# GPS_radiologger_v19.net
KiCad netlist of a schematic drawn in EAGLE
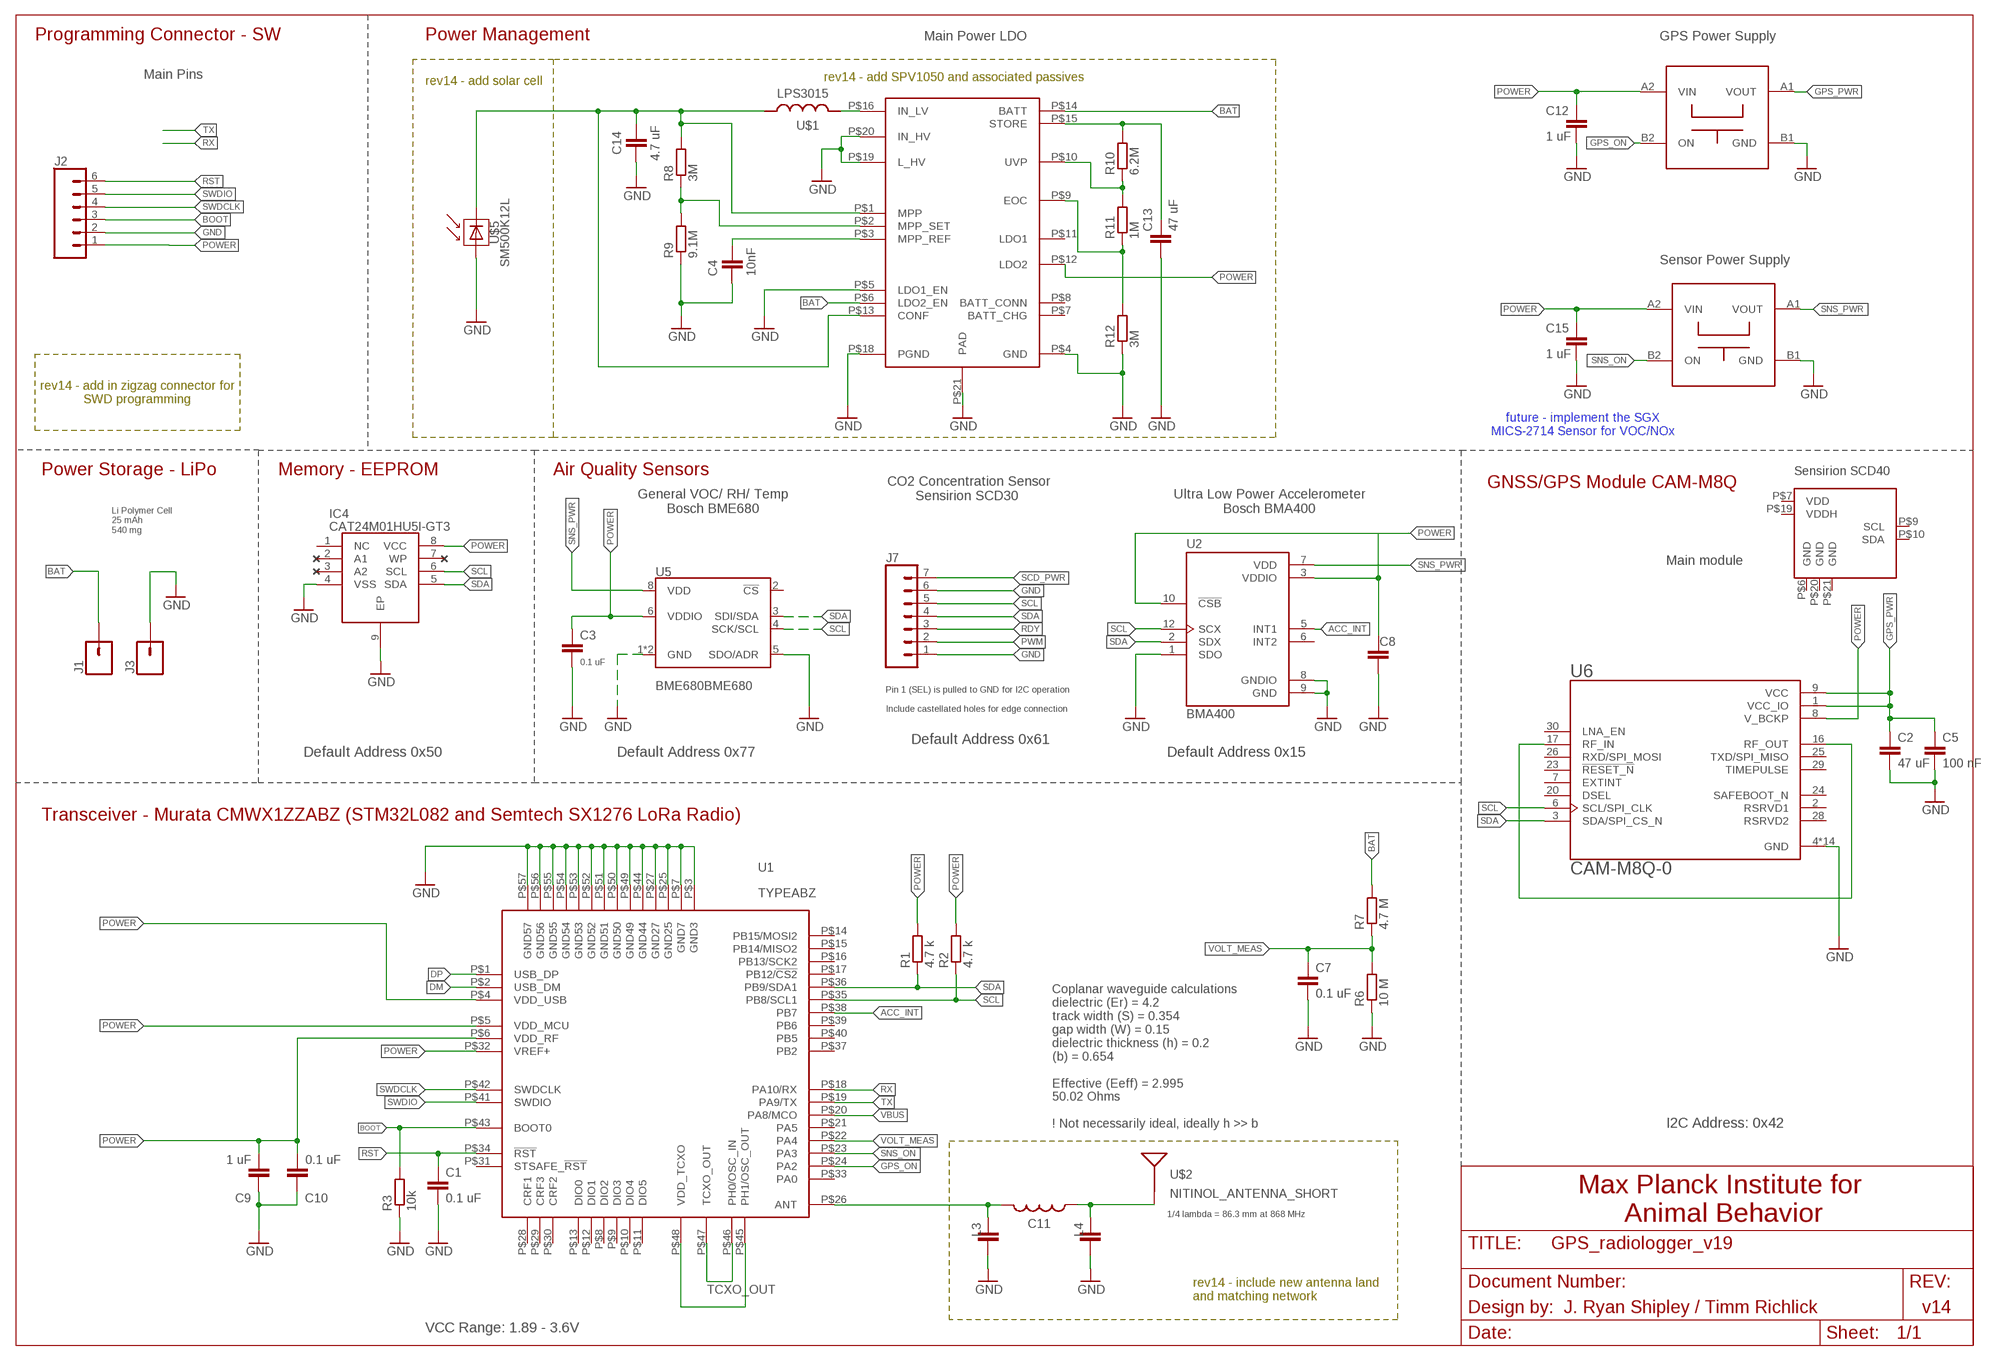
[diagram p0: schematic, sheet 1]

(export (version "E")
  (design (tool "Eeschema 10.0.6"))
  (components
    (comp (ref "C1")
      (value "0.1 uF")
      (footprint "eagle-import:C0201")
      (libsource (lib "eagle-import") (part "C-EUC0201"))
    )
    (comp (ref "C2")
      (value "47 uF")
      (footprint "eagle-import:C0201")
      (libsource (lib "eagle-import") (part "C-EUC0201"))
    )
    (comp (ref "C3")
      (value "0.1 uF")
      (footprint "eagle-import:C0201")
      (libsource (lib "eagle-import") (part "C-EUC0201"))
    )
    (comp (ref "C4")
      (value "10nF")
      (footprint "eagle-import:C0201")
      (libsource (lib "eagle-import") (part "C-EUC0201"))
    )
    (comp (ref "C5")
      (value "100 nF")
      (footprint "eagle-import:C0201")
      (libsource (lib "eagle-import") (part "C-EUC0201"))
    )
    (comp (ref "C7")
      (value "0.1 uF")
      (footprint "eagle-import:C0201")
      (libsource (lib "eagle-import") (part "C-EUC0201"))
    )
    (comp (ref "C8")
      (value "C-EUC0201")
      (footprint "eagle-import:C0201")
      (libsource (lib "eagle-import") (part "C-EUC0201"))
    )
    (comp (ref "C9")
      (value "1 uF")
      (footprint "eagle-import:C0201")
      (libsource (lib "eagle-import") (part "C-EUC0201"))
    )
    (comp (ref "C10")
      (value "0.1 uF")
      (footprint "eagle-import:C0201")
      (libsource (lib "eagle-import") (part "C-EUC0201"))
    )
    (comp (ref "C11")
      (value "0.1uF")
      (footprint "eagle-import:L0201")
      (libsource (lib "eagle-import") (part "L-USL0201"))
    )
    (comp (ref "C12")
      (value "1 uF")
      (footprint "eagle-import:C0201")
      (libsource (lib "eagle-import") (part "C-EUC0201"))
    )
    (comp (ref "C13")
      (value "47 uF")
      (footprint "eagle-import:C0805K")
      (libsource (lib "eagle-import") (part "C-EUC0805K"))
    )
    (comp (ref "C14")
      (value "4.7 uF")
      (footprint "eagle-import:C0201")
      (libsource (lib "eagle-import") (part "C-EUC0201"))
    )
    (comp (ref "C15")
      (value "1 uF")
      (footprint "eagle-import:C0201")
      (libsource (lib "eagle-import") (part "C-EUC0201"))
    )
    (comp (ref "IC4")
      (value "CAT24M01HU5I-GT3")
      (footprint "eagle-import:SON50P300X200X55-9N")
      (fields
        (field (name "MOUSER_PART_NUMBER") "863-CAT24M01HU5I-GT3")
        (field (name "RS_PART_NUMBER") "7814831P")
      )
      (libsource (lib "eagle-import") (part "CAT24M01HU5I-GT3"))
    )
    (comp (ref "J1")
      (value "CONN_01PTH_NO_SILK_YES_STOP")
      (footprint "eagle-import:1X01_NO_SILK")
      (libsource (lib "eagle-import") (part "CONN_01PTH_NO_SILK_YES_STOP"))
    )
    (comp (ref "J2")
      (value "CONN_06NO_SILK_NO_POP")
      (footprint "eagle-import:1X06_NO_SILK")
      (libsource (lib "eagle-import") (part "CONN_06NO_SILK_NO_POP"))
    )
    (comp (ref "J3")
      (value "CONN_01PTH_NO_SILK_YES_STOP")
      (footprint "eagle-import:1X01_NO_SILK")
      (libsource (lib "eagle-import") (part "CONN_01PTH_NO_SILK_YES_STOP"))
    )
    (comp (ref "J7")
      (value "CONN_07NO_SILK")
      (footprint "eagle-import:1X07_NO_SILK")
      (libsource (lib "eagle-import") (part "CONN_07NO_SILK"))
    )
    (comp (ref "L3")
      (value "C-EUC0201")
      (footprint "eagle-import:C0201")
      (libsource (lib "eagle-import") (part "C-EUC0201"))
    )
    (comp (ref "L4")
      (value "C-EUC0201")
      (footprint "eagle-import:C0201")
      (libsource (lib "eagle-import") (part "C-EUC0201"))
    )
    (comp (ref "R1")
      (value "4.7 k")
      (footprint "eagle-import:R0201")
      (libsource (lib "eagle-import") (part "R-EU_R0201"))
    )
    (comp (ref "R2")
      (value "4.7 k")
      (footprint "eagle-import:R0201")
      (libsource (lib "eagle-import") (part "R-EU_R0201"))
    )
    (comp (ref "R3")
      (value "10k")
      (footprint "eagle-import:R0201")
      (libsource (lib "eagle-import") (part "R-EU_R0201"))
    )
    (comp (ref "R6")
      (value "10 M")
      (footprint "eagle-import:R0201")
      (libsource (lib "eagle-import") (part "R-EU_R0201"))
    )
    (comp (ref "R7")
      (value "4.7 M")
      (footprint "eagle-import:R0201")
      (libsource (lib "eagle-import") (part "R-EU_R0201"))
    )
    (comp (ref "R8")
      (value "3M")
      (footprint "eagle-import:R0201")
      (libsource (lib "eagle-import") (part "R-EU_R0201"))
    )
    (comp (ref "R9")
      (value "9.1M")
      (footprint "eagle-import:R0201")
      (libsource (lib "eagle-import") (part "R-EU_R0201"))
    )
    (comp (ref "R10")
      (value "6.2M")
      (footprint "eagle-import:R0201")
      (libsource (lib "eagle-import") (part "R-EU_R0201"))
    )
    (comp (ref "R11")
      (value "1M")
      (footprint "eagle-import:R0201")
      (libsource (lib "eagle-import") (part "R-EU_R0201"))
    )
    (comp (ref "R12")
      (value "3M")
      (footprint "eagle-import:R0201")
      (libsource (lib "eagle-import") (part "R-EU_R0201"))
    )
    (comp (ref "U$1")
      (value "LPS3015")
      (footprint "eagle-import:LPS_3015")
      (libsource (lib "eagle-import") (part "LPS3015"))
    )
    (comp (ref "U$2")
      (value "NITINOL_ANTENNA_SHORT")
      (footprint "eagle-import:ICARUS_NITINOL_ANTENNA_SHORT")
      (libsource (lib "eagle-import") (part "NITINOL_ANTENNA_SHORT"))
    )
    (comp (ref "U$3")
      (value "TPS22916CL")
      (footprint "eagle-import:YFP0004-DSBGA")
      (libsource (lib "eagle-import") (part "TPS22916CL"))
    )
    (comp (ref "U$4")
      (value "TPS22916CL")
      (footprint "eagle-import:YFP0004-DSBGA")
      (libsource (lib "eagle-import") (part "TPS22916CL"))
    )
    (comp (ref "U$5")
      (value "SM500K12L")
      (footprint "eagle-import:SM500K12L")
      (libsource (lib "eagle-import") (part "SM500K12L"))
    )
    (comp (ref "U$6")
      (value "SCD40")
      (footprint "eagle-import:SCD40_LGA")
      (libsource (lib "eagle-import") (part "SCD40"))
    )
    (comp (ref "U1")
      (value "TYPEABZ")
      (footprint "eagle-import:TYPEABZ")
      (libsource (lib "eagle-import") (part "TYPEABZ"))
    )
    (comp (ref "U2")
      (value "BMA400")
      (footprint "eagle-import:XDCR_BMA400")
      (fields (field (name "MF") "Bosch Sensortec"))
      (libsource (lib "eagle-import") (part "BMA400"))
    )
    (comp (ref "U4")
      (value "SPV1050")
      (footprint "eagle-import:SPV1050")
      (libsource (lib "eagle-import") (part "SPV1050"))
    )
    (comp (ref "U5")
      (value "BME680BME680")
      (footprint "eagle-import:LGA3.0X3.0")
      (libsource (lib "eagle-import") (part "BME680BME680"))
    )
    (comp (ref "U6")
      (value "CAM-M8Q-0")
      (footprint "eagle-import:LCC100P960X1400X210-31N")
      (fields (field (name "MF") "U-Blox America"))
      (libsource (lib "eagle-import") (part "CAM-M8Q-0"))
    )
  )
  (nets
    (net (code "1") (name "/TCXO_OUT") (class "Default")
      (node (ref "U1") (pin "P$46") (pinfunction "PH0/OSC_IN_P$46") (pintype "bidirectional"))
      (node (ref "U1") (pin "P$47") (pinfunction "TCXO_OUT_P$47") (pintype "bidirectional"))
    )
    (net (code "2") (name "ACC_INT") (class "Default")
      (node (ref "U1") (pin "P$38") (pinfunction "PB7_P$38") (pintype "bidirectional"))
      (node (ref "U2") (pin "5") (pinfunction "INT1_5") (pintype "bidirectional"))
    )
    (net (code "3") (name "BAT") (class "Default")
      (node (ref "J1") (pin "1") (pinfunction "1_1") (pintype "passive"))
      (node (ref "R7") (pin "2") (pinfunction "2_2") (pintype "passive"))
      (node (ref "U4") (pin "P$14") (pinfunction "BATT_P$14") (pintype "bidirectional"))
      (node (ref "U4") (pin "P$6") (pinfunction "LDO2_EN_P$6") (pintype "input"))
    )
    (net (code "4") (name "BOOT") (class "Default")
      (node (ref "J2") (pin "3") (pinfunction "3_3") (pintype "passive"))
      (node (ref "R3") (pin "2") (pinfunction "2_2") (pintype "passive"))
      (node (ref "U1") (pin "P$43") (pinfunction "BOOT0_P$43") (pintype "bidirectional"))
    )
    (net (code "5") (name "DM") (class "Default")
      (node (ref "U1") (pin "P$2") (pinfunction "USB_DM_P$2") (pintype "bidirectional"))
    )
    (net (code "6") (name "DP") (class "Default")
      (node (ref "U1") (pin "P$1") (pinfunction "USB_DP_P$1") (pintype "bidirectional"))
    )
    (net (code "7") (name "GND") (class "Default")
      (node (ref "C1") (pin "2") (pinfunction "2_2") (pintype "passive"))
      (node (ref "C10") (pin "1") (pinfunction "1_1") (pintype "passive"))
      (node (ref "C12") (pin "2") (pinfunction "2_2") (pintype "passive"))
      (node (ref "C13") (pin "2") (pinfunction "2_2") (pintype "passive"))
      (node (ref "C14") (pin "2") (pinfunction "2_2") (pintype "passive"))
      (node (ref "C15") (pin "2") (pinfunction "2_2") (pintype "passive"))
      (node (ref "C2") (pin "2") (pinfunction "2_2") (pintype "passive"))
      (node (ref "C3") (pin "2") (pinfunction "2_2") (pintype "passive"))
      (node (ref "C4") (pin "2") (pinfunction "2_2") (pintype "passive"))
      (node (ref "C5") (pin "2") (pinfunction "2_2") (pintype "passive"))
      (node (ref "C7") (pin "2") (pinfunction "2_2") (pintype "passive"))
      (node (ref "C8") (pin "2") (pinfunction "2_2") (pintype "passive"))
      (node (ref "C9") (pin "1") (pinfunction "1_1") (pintype "passive"))
      (node (ref "IC4") (pin "4") (pinfunction "VSS_4") (pintype "power_in"))
      (node (ref "IC4") (pin "9") (pinfunction "EP_9") (pintype "bidirectional"))
      (node (ref "J2") (pin "2") (pinfunction "2_2") (pintype "passive"))
      (node (ref "J3") (pin "1") (pinfunction "1_1") (pintype "passive"))
      (node (ref "J7") (pin "1") (pinfunction "1_1") (pintype "passive"))
      (node (ref "J7") (pin "6") (pinfunction "6_6") (pintype "passive"))
      (node (ref "L3") (pin "2") (pinfunction "2_2") (pintype "passive"))
      (node (ref "L4") (pin "2") (pinfunction "2_2") (pintype "passive"))
      (node (ref "R12") (pin "1") (pinfunction "1_1") (pintype "passive"))
      (node (ref "R3") (pin "1") (pinfunction "1_1") (pintype "passive"))
      (node (ref "R6") (pin "1") (pinfunction "1_1") (pintype "passive"))
      (node (ref "R9") (pin "1") (pinfunction "1_1") (pintype "passive"))
      (node (ref "U$3") (pin "B1") (pinfunction "GND_B1") (pintype "bidirectional"))
      (node (ref "U$4") (pin "B1") (pinfunction "GND_B1") (pintype "bidirectional"))
      (node (ref "U$5") (pin "P$2") (pinfunction "MINUS_P$2") (pintype "passive"))
      (node (ref "U1") (pin "P$25") (pinfunction "GND25_P$25") (pintype "power_in"))
      (node (ref "U1") (pin "P$27") (pinfunction "GND27_P$27") (pintype "power_in"))
      (node (ref "U1") (pin "P$3") (pinfunction "GND3_P$3") (pintype "power_in"))
      (node (ref "U1") (pin "P$44") (pinfunction "GND44_P$44") (pintype "power_in"))
      (node (ref "U1") (pin "P$49") (pinfunction "GND49_P$49") (pintype "power_in"))
      (node (ref "U1") (pin "P$50") (pinfunction "GND50_P$50") (pintype "power_in"))
      (node (ref "U1") (pin "P$51") (pinfunction "GND51_P$51") (pintype "power_in"))
      (node (ref "U1") (pin "P$52") (pinfunction "GND52_P$52") (pintype "power_in"))
      (node (ref "U1") (pin "P$53") (pinfunction "GND53_P$53") (pintype "power_in"))
      (node (ref "U1") (pin "P$54") (pinfunction "GND54_P$54") (pintype "power_in"))
      (node (ref "U1") (pin "P$55") (pinfunction "GND55_P$55") (pintype "power_in"))
      (node (ref "U1") (pin "P$56") (pinfunction "GND56_P$56") (pintype "power_in"))
      (node (ref "U1") (pin "P$57") (pinfunction "GND57_P$57") (pintype "power_in"))
      (node (ref "U1") (pin "P$7") (pinfunction "GND7_P$7") (pintype "power_in"))
      (node (ref "U2") (pin "1") (pinfunction "SDO_1") (pintype "bidirectional"))
      (node (ref "U2") (pin "8") (pinfunction "GNDIO_8") (pintype "power_in"))
      (node (ref "U2") (pin "9") (pinfunction "GND_9") (pintype "power_in"))
      (node (ref "U4") (pin "P$18") (pinfunction "PGND_P$18") (pintype "power_in"))
      (node (ref "U4") (pin "P$19") (pinfunction "L_HV_P$19") (pintype "power_in"))
      (node (ref "U4") (pin "P$20") (pinfunction "IN_HV_P$20") (pintype "power_in"))
      (node (ref "U4") (pin "P$21") (pinfunction "PAD_P$21") (pintype "power_in"))
      (node (ref "U4") (pin "P$4") (pinfunction "GND_P$4") (pintype "power_in"))
      (node (ref "U4") (pin "P$5") (pinfunction "LDO1_EN_P$5") (pintype "input"))
      (node (ref "U5") (pin "1") (pinfunction "GND_1") (pintype "bidirectional"))
      (node (ref "U5") (pin "5") (pinfunction "SDO/ADR_5") (pintype "bidirectional"))
      (node (ref "U5") (pin "7") (pinfunction "GND_7") (pintype "bidirectional"))
      (node (ref "U6") (pin "10") (pinfunction "GND_10") (pintype "power_in"))
      (node (ref "U6") (pin "11") (pinfunction "GND_11") (pintype "power_in"))
      (node (ref "U6") (pin "12") (pinfunction "GND_12") (pintype "power_in"))
      (node (ref "U6") (pin "13") (pinfunction "GND_13") (pintype "power_in"))
      (node (ref "U6") (pin "14") (pinfunction "GND_14") (pintype "power_in"))
      (node (ref "U6") (pin "15") (pinfunction "GND_15") (pintype "power_in"))
      (node (ref "U6") (pin "18") (pinfunction "GND_18") (pintype "power_in"))
      (node (ref "U6") (pin "19") (pinfunction "GND_19") (pintype "power_in"))
      (node (ref "U6") (pin "21") (pinfunction "GND_21") (pintype "power_in"))
      (node (ref "U6") (pin "22") (pinfunction "GND_22") (pintype "power_in"))
      (node (ref "U6") (pin "27") (pinfunction "GND_27") (pintype "power_in"))
      (node (ref "U6") (pin "31") (pinfunction "GND_31") (pintype "power_in"))
      (node (ref "U6") (pin "4") (pinfunction "GND_4") (pintype "power_in"))
      (node (ref "U6") (pin "5") (pinfunction "GND_5") (pintype "power_in"))
    )
    (net (code "8") (name "GPS_ON") (class "Default")
      (node (ref "U$3") (pin "B2") (pinfunction "ON_B2") (pintype "bidirectional"))
      (node (ref "U1") (pin "P$24") (pinfunction "PA2_P$24") (pintype "bidirectional"))
    )
    (net (code "9") (name "GPS_PWR") (class "Default")
      (node (ref "C2") (pin "1") (pinfunction "1_1") (pintype "passive"))
      (node (ref "C5") (pin "1") (pinfunction "1_1") (pintype "passive"))
      (node (ref "U$3") (pin "A1") (pinfunction "VOUT_A1") (pintype "bidirectional"))
      (node (ref "U6") (pin "1") (pinfunction "VCC_IO_1") (pintype "power_in"))
      (node (ref "U6") (pin "9") (pinfunction "VCC_9") (pintype "power_in"))
    )
    (net (code "10") (name "Net-(C11-Pad1)") (class "Default")
      (node (ref "C11") (pin "1") (pinfunction "1_1") (pintype "passive"))
      (node (ref "L4") (pin "1") (pinfunction "1_1") (pintype "passive"))
      (node (ref "U$2") (pin "1") (pinfunction "SIGNAL_1") (pintype "bidirectional"))
      (node (ref "U$2") (pin "2") (pinfunction "SIGNAL_2") (pintype "bidirectional"))
      (node (ref "U$2") (pin "3") (pinfunction "SIGNAL_3") (pintype "bidirectional"))
    )
    (net (code "11") (name "Net-(U$1-1)") (class "Default")
      (node (ref "C14") (pin "1") (pinfunction "1_1") (pintype "passive"))
      (node (ref "R8") (pin "2") (pinfunction "2_2") (pintype "passive"))
      (node (ref "U$1") (pin "P$1") (pinfunction "1_P$1") (pintype "passive"))
      (node (ref "U$5") (pin "P$1") (pinfunction "PLUS_P$1") (pintype "passive"))
      (node (ref "U4") (pin "P$1") (pinfunction "MPP_P$1") (pintype "input"))
      (node (ref "U4") (pin "P$13") (pinfunction "CONF_P$13") (pintype "input"))
    )
    (net (code "12") (name "Net-(U$1-2)") (class "Default")
      (node (ref "U$1") (pin "P$2") (pinfunction "2_P$2") (pintype "passive"))
      (node (ref "U4") (pin "P$16") (pinfunction "IN_LV_P$16") (pintype "power_in"))
    )
    (net (code "13") (name "Net-(U1-ANT)") (class "Default")
      (node (ref "C11") (pin "2") (pinfunction "2_2") (pintype "passive"))
      (node (ref "L3") (pin "1") (pinfunction "1_1") (pintype "passive"))
      (node (ref "U1") (pin "P$26") (pinfunction "ANT_P$26") (pintype "bidirectional"))
    )
    (net (code "14") (name "Net-(U1-PH1{slash}OSC_OUT)") (class "Default")
      (node (ref "U1") (pin "P$45") (pinfunction "PH1/OSC_OUT_P$45") (pintype "bidirectional"))
      (node (ref "U1") (pin "P$48") (pinfunction "VDD_TCXO_P$48") (pintype "power_in"))
    )
    (net (code "15") (name "Net-(U2-VDDIO)") (class "Default")
      (node (ref "C8") (pin "1") (pinfunction "1_1") (pintype "passive"))
      (node (ref "U2") (pin "3") (pinfunction "VDDIO_3") (pintype "power_in"))
    )
    (net (code "16") (name "Net-(U4-EOC)") (class "Default")
      (node (ref "R11") (pin "1") (pinfunction "1_1") (pintype "passive"))
      (node (ref "R12") (pin "2") (pinfunction "2_2") (pintype "passive"))
      (node (ref "U4") (pin "P$9") (pinfunction "EOC_P$9") (pintype "input"))
    )
    (net (code "17") (name "Net-(U4-MPP_REF)") (class "Default")
      (node (ref "C4") (pin "1") (pinfunction "1_1") (pintype "passive"))
      (node (ref "U4") (pin "P$3") (pinfunction "MPP_REF_P$3") (pintype "input"))
    )
    (net (code "18") (name "Net-(U4-MPP_SET)") (class "Default")
      (node (ref "R8") (pin "1") (pinfunction "1_1") (pintype "passive"))
      (node (ref "R9") (pin "2") (pinfunction "2_2") (pintype "passive"))
      (node (ref "U4") (pin "P$2") (pinfunction "MPP_SET_P$2") (pintype "input"))
    )
    (net (code "19") (name "Net-(U4-STORE)") (class "Default")
      (node (ref "C13") (pin "1") (pinfunction "1_1") (pintype "passive"))
      (node (ref "R10") (pin "2") (pinfunction "2_2") (pintype "passive"))
      (node (ref "U4") (pin "P$15") (pinfunction "STORE_P$15") (pintype "bidirectional"))
    )
    (net (code "20") (name "Net-(U4-UVP)") (class "Default")
      (node (ref "R10") (pin "1") (pinfunction "1_1") (pintype "passive"))
      (node (ref "R11") (pin "2") (pinfunction "2_2") (pintype "passive"))
      (node (ref "U4") (pin "P$10") (pinfunction "UVP_P$10") (pintype "input"))
    )
    (net (code "21") (name "Net-(U6-RF_IN)") (class "Default")
      (node (ref "U6") (pin "16") (pinfunction "RF_OUT_16") (pintype "output"))
      (node (ref "U6") (pin "17") (pinfunction "RF_IN_17") (pintype "input"))
    )
    (net (code "22") (name "POWER") (class "Default")
      (node (ref "C10") (pin "2") (pinfunction "2_2") (pintype "passive"))
      (node (ref "C12") (pin "1") (pinfunction "1_1") (pintype "passive"))
      (node (ref "C15") (pin "1") (pinfunction "1_1") (pintype "passive"))
      (node (ref "C3") (pin "1") (pinfunction "1_1") (pintype "passive"))
      (node (ref "C9") (pin "2") (pinfunction "2_2") (pintype "passive"))
      (node (ref "IC4") (pin "8") (pinfunction "VCC_8") (pintype "power_in"))
      (node (ref "J2") (pin "1") (pinfunction "1_1") (pintype "passive"))
      (node (ref "R1") (pin "2") (pinfunction "2_2") (pintype "passive"))
      (node (ref "R2") (pin "2") (pinfunction "2_2") (pintype "passive"))
      (node (ref "U$3") (pin "A2") (pinfunction "VIN_A2") (pintype "bidirectional"))
      (node (ref "U$4") (pin "A2") (pinfunction "VIN_A2") (pintype "bidirectional"))
      (node (ref "U1") (pin "P$32") (pinfunction "VREF+_P$32") (pintype "power_in"))
      (node (ref "U1") (pin "P$4") (pinfunction "VDD_USB_P$4") (pintype "power_in"))
      (node (ref "U1") (pin "P$5") (pinfunction "VDD_MCU_P$5") (pintype "power_in"))
      (node (ref "U1") (pin "P$6") (pinfunction "VDD_RF_P$6") (pintype "power_in"))
      (node (ref "U2") (pin "10") (pinfunction "~{CSB}_10") (pintype "input"))
      (node (ref "U4") (pin "P$12") (pinfunction "LDO2_P$12") (pintype "output"))
      (node (ref "U5") (pin "6") (pinfunction "VDDIO_6") (pintype "bidirectional"))
      (node (ref "U6") (pin "8") (pinfunction "V_BCKP_8") (pintype "power_in"))
    )
    (net (code "23") (name "PWM") (class "Default")
      (node (ref "J7") (pin "2") (pinfunction "2_2") (pintype "passive"))
    )
    (net (code "24") (name "RDY") (class "Default")
      (node (ref "J7") (pin "3") (pinfunction "3_3") (pintype "passive"))
    )
    (net (code "25") (name "RST") (class "Default")
      (node (ref "C1") (pin "1") (pinfunction "1_1") (pintype "passive"))
      (node (ref "J2") (pin "6") (pinfunction "6_6") (pintype "passive"))
      (node (ref "U1") (pin "P$34") (pinfunction "~{RST}_P$34") (pintype "bidirectional"))
    )
    (net (code "26") (name "RX") (class "Default")
      (node (ref "U1") (pin "P$18") (pinfunction "PA10/RX_P$18") (pintype "bidirectional"))
    )
    (net (code "27") (name "SCD_PWR") (class "Default")
      (node (ref "J7") (pin "7") (pinfunction "7_7") (pintype "passive"))
    )
    (net (code "28") (name "SCL") (class "Default")
      (node (ref "IC4") (pin "6") (pinfunction "SCL_6") (pintype "bidirectional"))
      (node (ref "J7") (pin "5") (pinfunction "5_5") (pintype "passive"))
      (node (ref "R2") (pin "1") (pinfunction "1_1") (pintype "passive"))
      (node (ref "U1") (pin "P$35") (pinfunction "PB8/SCL1_P$35") (pintype "bidirectional"))
      (node (ref "U2") (pin "12") (pinfunction "SCX_12") (pintype "input"))
      (node (ref "U5") (pin "4") (pinfunction "SCK/SCL_4") (pintype "bidirectional"))
      (node (ref "U6") (pin "6") (pinfunction "SCL/SPI_CLK_6") (pintype "input"))
    )
    (net (code "29") (name "SDA") (class "Default")
      (node (ref "IC4") (pin "5") (pinfunction "SDA_5") (pintype "bidirectional"))
      (node (ref "J7") (pin "4") (pinfunction "4_4") (pintype "passive"))
      (node (ref "R1") (pin "1") (pinfunction "1_1") (pintype "passive"))
      (node (ref "U1") (pin "P$36") (pinfunction "PB9/SDA1_P$36") (pintype "bidirectional"))
      (node (ref "U2") (pin "2") (pinfunction "SDX_2") (pintype "bidirectional"))
      (node (ref "U5") (pin "3") (pinfunction "SDI/SDA_3") (pintype "bidirectional"))
      (node (ref "U6") (pin "3") (pinfunction "SDA/SPI_CS_N_3") (pintype "bidirectional"))
    )
    (net (code "30") (name "SNS_ON") (class "Default")
      (node (ref "U$4") (pin "B2") (pinfunction "ON_B2") (pintype "bidirectional"))
      (node (ref "U1") (pin "P$23") (pinfunction "PA3_P$23") (pintype "bidirectional"))
    )
    (net (code "31") (name "SNS_PWR") (class "Default")
      (node (ref "U$4") (pin "A1") (pinfunction "VOUT_A1") (pintype "bidirectional"))
      (node (ref "U2") (pin "7") (pinfunction "VDD_7") (pintype "power_in"))
      (node (ref "U5") (pin "8") (pinfunction "VDD_8") (pintype "bidirectional"))
    )
    (net (code "32") (name "SWDCLK") (class "Default")
      (node (ref "J2") (pin "4") (pinfunction "4_4") (pintype "passive"))
      (node (ref "U1") (pin "P$42") (pinfunction "SWDCLK_P$42") (pintype "bidirectional"))
    )
    (net (code "33") (name "SWDIO") (class "Default")
      (node (ref "J2") (pin "5") (pinfunction "5_5") (pintype "passive"))
      (node (ref "U1") (pin "P$41") (pinfunction "SWDIO_P$41") (pintype "bidirectional"))
    )
    (net (code "34") (name "TX") (class "Default")
      (node (ref "U1") (pin "P$19") (pinfunction "PA9/TX_P$19") (pintype "bidirectional"))
    )
    (net (code "35") (name "VBUS") (class "Default")
      (node (ref "U1") (pin "P$20") (pinfunction "PA8/MCO_P$20") (pintype "bidirectional"))
    )
    (net (code "36") (name "VOLT_MEAS") (class "Default")
      (node (ref "C7") (pin "1") (pinfunction "1_1") (pintype "passive"))
      (node (ref "R6") (pin "2") (pinfunction "2_2") (pintype "passive"))
      (node (ref "R7") (pin "1") (pinfunction "1_1") (pintype "passive"))
      (node (ref "U1") (pin "P$22") (pinfunction "PA4_P$22") (pintype "bidirectional"))
    )
    (net (code "37") (name "unconnected-(IC4-A1-Pad2)") (class "Default")
      (node (ref "IC4") (pin "2") (pinfunction "A1_2") (pintype "bidirectional"))
    )
    (net (code "38") (name "unconnected-(IC4-A2-Pad3)") (class "Default")
      (node (ref "IC4") (pin "3") (pinfunction "A2_3") (pintype "bidirectional"))
    )
    (net (code "39") (name "unconnected-(IC4-NC-Pad1)") (class "Default")
      (node (ref "IC4") (pin "1") (pinfunction "NC_1") (pintype "no_connect"))
    )
    (net (code "40") (name "unconnected-(IC4-WP-Pad7)") (class "Default")
      (node (ref "IC4") (pin "7") (pinfunction "WP_7") (pintype "bidirectional"))
    )
    (net (code "41") (name "unconnected-(U$6-GND-PadP$6)") (class "Default")
      (node (ref "U$6") (pin "P$6") (pinfunction "GND_P$6") (pintype "bidirectional"))
    )
    (net (code "42") (name "unconnected-(U$6-GND-PadP$20)") (class "Default")
      (node (ref "U$6") (pin "P$20") (pinfunction "GND_P$20") (pintype "bidirectional"))
    )
    (net (code "43") (name "unconnected-(U$6-GND-PadP$21)") (class "Default")
      (node (ref "U$6") (pin "P$21") (pinfunction "GND_P$21") (pintype "bidirectional"))
    )
    (net (code "44") (name "unconnected-(U$6-SCL-PadP$9)") (class "Default")
      (node (ref "U$6") (pin "P$9") (pinfunction "SCL_P$9") (pintype "bidirectional"))
    )
    (net (code "45") (name "unconnected-(U$6-SDA-PadP$10)") (class "Default")
      (node (ref "U$6") (pin "P$10") (pinfunction "SDA_P$10") (pintype "bidirectional"))
    )
    (net (code "46") (name "unconnected-(U$6-VDD-PadP$7)") (class "Default")
      (node (ref "U$6") (pin "P$7") (pinfunction "VDD_P$7") (pintype "bidirectional"))
    )
    (net (code "47") (name "unconnected-(U$6-VDDH-PadP$19)") (class "Default")
      (node (ref "U$6") (pin "P$19") (pinfunction "VDDH_P$19") (pintype "bidirectional"))
    )
    (net (code "48") (name "unconnected-(U1-CRF1-PadP$28)") (class "Default")
      (node (ref "U1") (pin "P$28") (pinfunction "CRF1_P$28") (pintype "no_connect"))
    )
    (net (code "49") (name "unconnected-(U1-CRF2-PadP$30)") (class "Default")
      (node (ref "U1") (pin "P$30") (pinfunction "CRF2_P$30") (pintype "no_connect"))
    )
    (net (code "50") (name "unconnected-(U1-CRF3-PadP$29)") (class "Default")
      (node (ref "U1") (pin "P$29") (pinfunction "CRF3_P$29") (pintype "no_connect"))
    )
    (net (code "51") (name "unconnected-(U1-DIO0-PadP$13)") (class "Default")
      (node (ref "U1") (pin "P$13") (pinfunction "DIO0_P$13") (pintype "no_connect"))
    )
    (net (code "52") (name "unconnected-(U1-DIO1-PadP$12)") (class "Default")
      (node (ref "U1") (pin "P$12") (pinfunction "DIO1_P$12") (pintype "no_connect"))
    )
    (net (code "53") (name "unconnected-(U1-DIO2-PadP$8)") (class "Default")
      (node (ref "U1") (pin "P$8") (pinfunction "DIO2_P$8") (pintype "no_connect"))
    )
    (net (code "54") (name "unconnected-(U1-DIO3-PadP$9)") (class "Default")
      (node (ref "U1") (pin "P$9") (pinfunction "DIO3_P$9") (pintype "no_connect"))
    )
    (net (code "55") (name "unconnected-(U1-DIO4-PadP$10)") (class "Default")
      (node (ref "U1") (pin "P$10") (pinfunction "DIO4_P$10") (pintype "bidirectional"))
    )
    (net (code "56") (name "unconnected-(U1-DIO5-PadP$11)") (class "Default")
      (node (ref "U1") (pin "P$11") (pinfunction "DIO5_P$11") (pintype "bidirectional"))
    )
    (net (code "57") (name "unconnected-(U1-PA0-PadP$33)") (class "Default")
      (node (ref "U1") (pin "P$33") (pinfunction "PA0_P$33") (pintype "bidirectional"))
    )
    (net (code "58") (name "unconnected-(U1-PA5-PadP$21)") (class "Default")
      (node (ref "U1") (pin "P$21") (pinfunction "PA5_P$21") (pintype "bidirectional"))
    )
    (net (code "59") (name "unconnected-(U1-PB2-PadP$37)") (class "Default")
      (node (ref "U1") (pin "P$37") (pinfunction "PB2_P$37") (pintype "bidirectional"))
    )
    (net (code "60") (name "unconnected-(U1-PB5-PadP$40)") (class "Default")
      (node (ref "U1") (pin "P$40") (pinfunction "PB5_P$40") (pintype "bidirectional"))
    )
    (net (code "61") (name "unconnected-(U1-PB6-PadP$39)") (class "Default")
      (node (ref "U1") (pin "P$39") (pinfunction "PB6_P$39") (pintype "bidirectional"))
    )
    (net (code "62") (name "unconnected-(U1-PB12{slash}~{CS2}-PadP$17)") (class "Default")
      (node (ref "U1") (pin "P$17") (pinfunction "PB12/~{CS2}_P$17") (pintype "bidirectional"))
    )
    (net (code "63") (name "unconnected-(U1-PB13{slash}SCK2-PadP$16)") (class "Default")
      (node (ref "U1") (pin "P$16") (pinfunction "PB13/SCK2_P$16") (pintype "bidirectional"))
    )
    (net (code "64") (name "unconnected-(U1-PB14{slash}MISO2-PadP$15)") (class "Default")
      (node (ref "U1") (pin "P$15") (pinfunction "PB14/MISO2_P$15") (pintype "bidirectional"))
    )
    (net (code "65") (name "unconnected-(U1-PB15{slash}MOSI2-PadP$14)") (class "Default")
      (node (ref "U1") (pin "P$14") (pinfunction "PB15/MOSI2_P$14") (pintype "bidirectional"))
    )
    (net (code "66") (name "unconnected-(U1-STSAFE_~{RST}-PadP$31)") (class "Default")
      (node (ref "U1") (pin "P$31") (pinfunction "STSAFE_~{RST}_P$31") (pintype "bidirectional"))
    )
    (net (code "67") (name "unconnected-(U2-INT2-Pad6)") (class "Default")
      (node (ref "U2") (pin "6") (pinfunction "INT2_6") (pintype "bidirectional"))
    )
    (net (code "68") (name "unconnected-(U4-BATT_CHG-PadP$7)") (class "Default")
      (node (ref "U4") (pin "P$7") (pinfunction "BATT_CHG_P$7") (pintype "open_collector"))
    )
    (net (code "69") (name "unconnected-(U4-BATT_CONN-PadP$8)") (class "Default")
      (node (ref "U4") (pin "P$8") (pinfunction "BATT_CONN_P$8") (pintype "open_collector"))
    )
    (net (code "70") (name "unconnected-(U4-LDO1-PadP$11)") (class "Default")
      (node (ref "U4") (pin "P$11") (pinfunction "LDO1_P$11") (pintype "output"))
    )
    (net (code "71") (name "unconnected-(U5-~{CS}-Pad2)") (class "Default")
      (node (ref "U5") (pin "2") (pinfunction "~{CS}_2") (pintype "bidirectional"))
    )
    (net (code "72") (name "unconnected-(U6-DSEL-Pad20)") (class "Default")
      (node (ref "U6") (pin "20") (pinfunction "DSEL_20") (pintype "input"))
    )
    (net (code "73") (name "unconnected-(U6-EXTINT-Pad7)") (class "Default")
      (node (ref "U6") (pin "7") (pinfunction "EXTINT_7") (pintype "input"))
    )
    (net (code "74") (name "unconnected-(U6-LNA_EN-Pad30)") (class "Default")
      (node (ref "U6") (pin "30") (pinfunction "LNA_EN_30") (pintype "input"))
    )
    (net (code "75") (name "unconnected-(U6-RSRVD1-Pad2)") (class "Default")
      (node (ref "U6") (pin "2") (pinfunction "RSRVD1_2") (pintype "passive"))
    )
    (net (code "76") (name "unconnected-(U6-RSRVD2-Pad28)") (class "Default")
      (node (ref "U6") (pin "28") (pinfunction "RSRVD2_28") (pintype "passive"))
    )
    (net (code "77") (name "unconnected-(U6-RXD{slash}SPI_MOSI-Pad26)") (class "Default")
      (node (ref "U6") (pin "26") (pinfunction "RXD/SPI_MOSI_26") (pintype "input"))
    )
    (net (code "78") (name "unconnected-(U6-SAFEBOOT_N-Pad24)") (class "Default")
      (node (ref "U6") (pin "24") (pinfunction "SAFEBOOT_N_24") (pintype "passive"))
    )
    (net (code "79") (name "unconnected-(U6-TIMEPULSE-Pad29)") (class "Default")
      (node (ref "U6") (pin "29") (pinfunction "TIMEPULSE_29") (pintype "output"))
    )
    (net (code "80") (name "unconnected-(U6-TXD{slash}SPI_MISO-Pad25)") (class "Default")
      (node (ref "U6") (pin "25") (pinfunction "TXD/SPI_MISO_25") (pintype "output"))
    )
    (net (code "81") (name "unconnected-(U6-~{RESET_N}-Pad23)") (class "Default")
      (node (ref "U6") (pin "23") (pinfunction "~{RESET_N}_23") (pintype "input"))
    )
  )
)
